# SWITCHING.net
KiCad netlist of a schematic drawn in Altium Designer
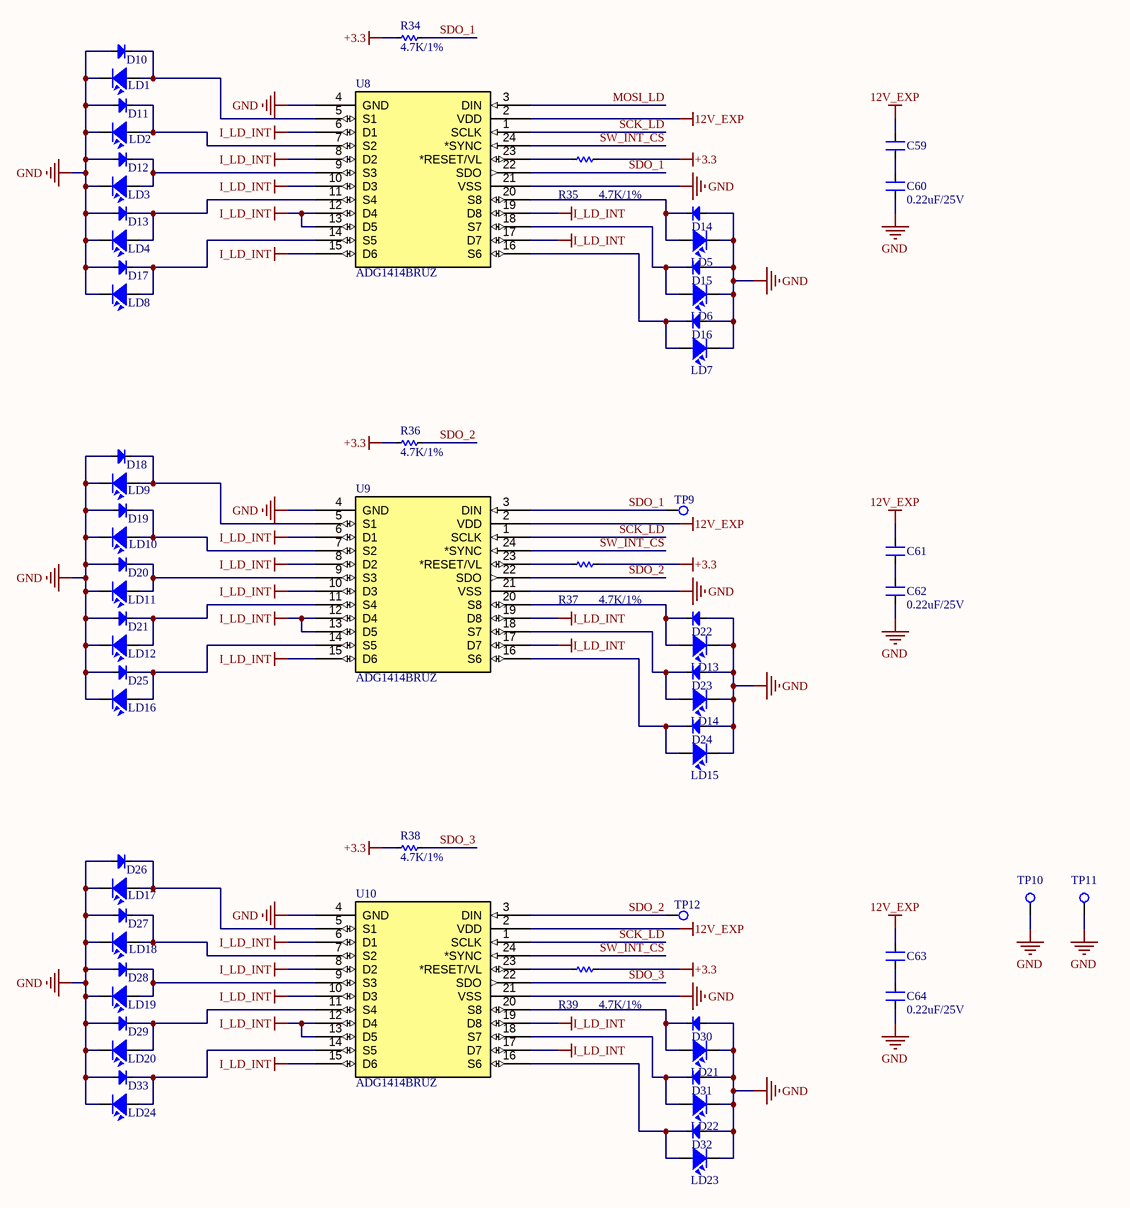
[diagram p0: SWITCHING.SchDoc]

(export (version "E")
  (design (tool "Eeschema 10.0.6"))
  (components
    (comp (ref "C59")
      (value "0.22uF/25V")
      (footprint "SM-0603")
      (description "CL10B224KA8NNNC")
      (libsource (lib "Capacitors") (part "CM"))
    )
    (comp (ref "C60")
      (value "0.22uF/25V")
      (footprint "SM-0603")
      (description "CL10B224KA8NNNC")
      (libsource (lib "Capacitors") (part "CM"))
    )
    (comp (ref "C61")
      (value "0.22uF/25V")
      (footprint "SM-0603")
      (description "CL10B224KA8NNNC")
      (libsource (lib "Capacitors") (part "CM"))
    )
    (comp (ref "C62")
      (value "0.22uF/25V")
      (footprint "SM-0603")
      (description "CL10B224KA8NNNC")
      (libsource (lib "Capacitors") (part "CM"))
    )
    (comp (ref "C63")
      (value "0.22uF/25V")
      (footprint "SM-0603")
      (description "CL10B224KA8NNNC")
      (libsource (lib "Capacitors") (part "CM"))
    )
    (comp (ref "C64")
      (value "0.22uF/25V")
      (footprint "SM-0603")
      (description "CL10B224KA8NNNC")
      (libsource (lib "Capacitors") (part "CM"))
    )
    (comp (ref "D10")
      (value "1N4148W-TP")
      (footprint "SOD23")
      (fields (field (name "PUBLISHER") "Altium Limited"))
      (libsource (lib "Library") (part "Diode SMD"))
    )
    (comp (ref "D11")
      (value "1N4148W-TP")
      (footprint "SOD23")
      (fields (field (name "PUBLISHER") "Altium Limited"))
      (libsource (lib "Library") (part "Diode SMD"))
    )
    (comp (ref "D12")
      (value "1N4148W-TP")
      (footprint "SOD23")
      (fields (field (name "PUBLISHER") "Altium Limited"))
      (libsource (lib "Library") (part "Diode SMD"))
    )
    (comp (ref "D13")
      (value "1N4148W-TP")
      (footprint "SOD23")
      (fields (field (name "PUBLISHER") "Altium Limited"))
      (libsource (lib "Library") (part "Diode SMD"))
    )
    (comp (ref "D14")
      (value "1N4148W-TP")
      (footprint "SOD23")
      (fields (field (name "PUBLISHER") "Altium Limited"))
      (libsource (lib "Library") (part "Diode SMD"))
    )
    (comp (ref "D15")
      (value "1N4148W-TP")
      (footprint "SOD23")
      (fields (field (name "PUBLISHER") "Altium Limited"))
      (libsource (lib "Library") (part "Diode SMD"))
    )
    (comp (ref "D16")
      (value "1N4148W-TP")
      (footprint "SOD23")
      (fields (field (name "PUBLISHER") "Altium Limited"))
      (libsource (lib "Library") (part "Diode SMD"))
    )
    (comp (ref "D17")
      (value "1N4148W-TP")
      (footprint "SOD23")
      (fields (field (name "PUBLISHER") "Altium Limited"))
      (libsource (lib "Library") (part "Diode SMD"))
    )
    (comp (ref "D18")
      (value "1N4148W-TP")
      (footprint "SOD23")
      (fields (field (name "PUBLISHER") "Altium Limited"))
      (libsource (lib "Library") (part "Diode SMD"))
    )
    (comp (ref "D19")
      (value "1N4148W-TP")
      (footprint "SOD23")
      (fields (field (name "PUBLISHER") "Altium Limited"))
      (libsource (lib "Library") (part "Diode SMD"))
    )
    (comp (ref "D20")
      (value "1N4148W-TP")
      (footprint "SOD23")
      (fields (field (name "PUBLISHER") "Altium Limited"))
      (libsource (lib "Library") (part "Diode SMD"))
    )
    (comp (ref "D21")
      (value "1N4148W-TP")
      (footprint "SOD23")
      (fields (field (name "PUBLISHER") "Altium Limited"))
      (libsource (lib "Library") (part "Diode SMD"))
    )
    (comp (ref "D22")
      (value "1N4148W-TP")
      (footprint "SOD23")
      (fields (field (name "PUBLISHER") "Altium Limited"))
      (libsource (lib "Library") (part "Diode SMD"))
    )
    (comp (ref "D23")
      (value "1N4148W-TP")
      (footprint "SOD23")
      (fields (field (name "PUBLISHER") "Altium Limited"))
      (libsource (lib "Library") (part "Diode SMD"))
    )
    (comp (ref "D24")
      (value "1N4148W-TP")
      (footprint "SOD23")
      (fields (field (name "PUBLISHER") "Altium Limited"))
      (libsource (lib "Library") (part "Diode SMD"))
    )
    (comp (ref "D25")
      (value "1N4148W-TP")
      (footprint "SOD23")
      (fields (field (name "PUBLISHER") "Altium Limited"))
      (libsource (lib "Library") (part "Diode SMD"))
    )
    (comp (ref "D26")
      (value "1N4148W-TP")
      (footprint "SOD23")
      (fields (field (name "PUBLISHER") "Altium Limited"))
      (libsource (lib "Library") (part "Diode SMD"))
    )
    (comp (ref "D27")
      (value "1N4148W-TP")
      (footprint "SOD23")
      (fields (field (name "PUBLISHER") "Altium Limited"))
      (libsource (lib "Library") (part "Diode SMD"))
    )
    (comp (ref "D28")
      (value "1N4148W-TP")
      (footprint "SOD23")
      (fields (field (name "PUBLISHER") "Altium Limited"))
      (libsource (lib "Library") (part "Diode SMD"))
    )
    (comp (ref "D29")
      (value "1N4148W-TP")
      (footprint "SOD23")
      (fields (field (name "PUBLISHER") "Altium Limited"))
      (libsource (lib "Library") (part "Diode SMD"))
    )
    (comp (ref "D30")
      (value "1N4148W-TP")
      (footprint "SOD23")
      (fields (field (name "PUBLISHER") "Altium Limited"))
      (libsource (lib "Library") (part "Diode SMD"))
    )
    (comp (ref "D31")
      (value "1N4148W-TP")
      (footprint "SOD23")
      (fields (field (name "PUBLISHER") "Altium Limited"))
      (libsource (lib "Library") (part "Diode SMD"))
    )
    (comp (ref "D32")
      (value "1N4148W-TP")
      (footprint "SOD23")
      (fields (field (name "PUBLISHER") "Altium Limited"))
      (libsource (lib "Library") (part "Diode SMD"))
    )
    (comp (ref "D33")
      (value "1N4148W-TP")
      (footprint "SOD23")
      (fields (field (name "PUBLISHER") "Altium Limited"))
      (libsource (lib "Library") (part "Diode SMD"))
    )
    (comp (ref "LD1")
      (value "LaserDiode")
      (footprint "LASER_SOCKET")
      (description "OPV302")
      (libsource (lib "Library_HUNG") (part "LD"))
    )
    (comp (ref "LD2")
      (value "LaserDiode")
      (footprint "LASER_SOCKET")
      (description "OPV302")
      (libsource (lib "Library_HUNG") (part "LD"))
    )
    (comp (ref "LD3")
      (value "LaserDiode")
      (footprint "LASER_SOCKET")
      (description "OPV302")
      (libsource (lib "Library_HUNG") (part "LD"))
    )
    (comp (ref "LD4")
      (value "LaserDiode")
      (footprint "LASER_SOCKET")
      (description "OPV302")
      (libsource (lib "Library_HUNG") (part "LD"))
    )
    (comp (ref "LD5")
      (value "LaserDiode")
      (footprint "LASER_SOCKET")
      (description "OPV302")
      (libsource (lib "Library_HUNG") (part "LD"))
    )
    (comp (ref "LD6")
      (value "LaserDiode")
      (footprint "LASER_SOCKET")
      (description "OPV302")
      (libsource (lib "Library_HUNG") (part "LD"))
    )
    (comp (ref "LD7")
      (value "LaserDiode")
      (footprint "LASER_SOCKET")
      (description "OPV302")
      (libsource (lib "Library_HUNG") (part "LD"))
    )
    (comp (ref "LD8")
      (value "LaserDiode")
      (footprint "LASER_SOCKET")
      (description "OPV302")
      (libsource (lib "Library_HUNG") (part "LD"))
    )
    (comp (ref "LD9")
      (value "LaserDiode")
      (footprint "LASER_SOCKET")
      (description "OPV302")
      (libsource (lib "Library_HUNG") (part "LD"))
    )
    (comp (ref "LD10")
      (value "LaserDiode")
      (footprint "LASER_SOCKET")
      (description "OPV302")
      (libsource (lib "Library_HUNG") (part "LD"))
    )
    (comp (ref "LD11")
      (value "LaserDiode")
      (footprint "LASER_SOCKET")
      (description "OPV302")
      (libsource (lib "Library_HUNG") (part "LD"))
    )
    (comp (ref "LD12")
      (value "LaserDiode")
      (footprint "LASER_SOCKET")
      (description "OPV302")
      (libsource (lib "Library_HUNG") (part "LD"))
    )
    (comp (ref "LD13")
      (value "LaserDiode")
      (footprint "LASER_SOCKET")
      (description "OPV302")
      (libsource (lib "Library_HUNG") (part "LD"))
    )
    (comp (ref "LD14")
      (value "LaserDiode")
      (footprint "LASER_SOCKET")
      (description "OPV302")
      (libsource (lib "Library_HUNG") (part "LD"))
    )
    (comp (ref "LD15")
      (value "LaserDiode")
      (footprint "LASER_SOCKET")
      (description "OPV302")
      (libsource (lib "Library_HUNG") (part "LD"))
    )
    (comp (ref "LD16")
      (value "LaserDiode")
      (footprint "LASER_SOCKET")
      (description "OPV302")
      (libsource (lib "Library_HUNG") (part "LD"))
    )
    (comp (ref "LD17")
      (value "LaserDiode")
      (footprint "LASER_SOCKET")
      (description "OPV302")
      (libsource (lib "Library_HUNG") (part "LD"))
    )
    (comp (ref "LD18")
      (value "LaserDiode")
      (footprint "LASER_SOCKET")
      (description "OPV302")
      (libsource (lib "Library_HUNG") (part "LD"))
    )
    (comp (ref "LD19")
      (value "LaserDiode")
      (footprint "LASER_SOCKET")
      (description "OPV302")
      (libsource (lib "Library_HUNG") (part "LD"))
    )
    (comp (ref "LD20")
      (value "LaserDiode")
      (footprint "LASER_SOCKET")
      (description "OPV302")
      (libsource (lib "Library_HUNG") (part "LD"))
    )
    (comp (ref "LD21")
      (value "LaserDiode")
      (footprint "LASER_SOCKET")
      (description "OPV302")
      (libsource (lib "Library_HUNG") (part "LD"))
    )
    (comp (ref "LD22")
      (value "LaserDiode")
      (footprint "LASER_SOCKET")
      (description "OPV302")
      (libsource (lib "Library_HUNG") (part "LD"))
    )
    (comp (ref "LD23")
      (value "LaserDiode")
      (footprint "LASER_SOCKET")
      (description "OPV302")
      (libsource (lib "Library_HUNG") (part "LD"))
    )
    (comp (ref "LD24")
      (value "LaserDiode")
      (footprint "LASER_SOCKET")
      (description "OPV302")
      (libsource (lib "Library_HUNG") (part "LD"))
    )
    (comp (ref "R34")
      (value "4.7K/1%")
      (footprint "RES-SMD-0603")
      (description "ERJ-3EKF4701V")
      (fields
        (field (name "MANUFACTURER") "Generic Components")
        (field (name "PUBLISHER") "Altium Hobart Technology Centre")
      )
      (libsource (lib "Library") (part "Res-SMD"))
    )
    (comp (ref "R35")
      (value "4.7K/1%")
      (footprint "RES-SMD-0603")
      (description "ERJ-3EKF4701V")
      (fields
        (field (name "MANUFACTURER") "Generic Components")
        (field (name "PUBLISHER") "Altium Hobart Technology Centre")
      )
      (libsource (lib "Library") (part "Res-SMD"))
    )
    (comp (ref "R36")
      (value "4.7K/1%")
      (footprint "RES-SMD-0603")
      (description "ERJ-3EKF4701V")
      (fields
        (field (name "MANUFACTURER") "Generic Components")
        (field (name "PUBLISHER") "Altium Hobart Technology Centre")
      )
      (libsource (lib "Library") (part "Res-SMD"))
    )
    (comp (ref "R37")
      (value "4.7K/1%")
      (footprint "RES-SMD-0603")
      (description "ERJ-3EKF4701V")
      (fields
        (field (name "MANUFACTURER") "Generic Components")
        (field (name "PUBLISHER") "Altium Hobart Technology Centre")
      )
      (libsource (lib "Library") (part "Res-SMD"))
    )
    (comp (ref "R38")
      (value "4.7K/1%")
      (footprint "RES-SMD-0603")
      (description "ERJ-3EKF4701V")
      (fields
        (field (name "MANUFACTURER") "Generic Components")
        (field (name "PUBLISHER") "Altium Hobart Technology Centre")
      )
      (libsource (lib "Library") (part "Res-SMD"))
    )
    (comp (ref "R39")
      (value "4.7K/1%")
      (footprint "RES-SMD-0603")
      (description "ERJ-3EKF4701V")
      (fields
        (field (name "MANUFACTURER") "Generic Components")
        (field (name "PUBLISHER") "Altium Hobart Technology Centre")
      )
      (libsource (lib "Library") (part "Res-SMD"))
    )
    (comp (ref "TP9")
      (value "Test_Point")
      (footprint "TESTPOINT")
      (libsource (lib "Library_HUNG") (part "Test_Point"))
    )
    (comp (ref "TP10")
      (value "Test_Point")
      (footprint "TESTPOINT")
      (libsource (lib "Library_HUNG") (part "Test_Point"))
    )
    (comp (ref "TP11")
      (value "Test_Point")
      (footprint "TESTPOINT")
      (libsource (lib "Library_HUNG") (part "Test_Point"))
    )
    (comp (ref "TP12")
      (value "Test_Point")
      (footprint "TESTPOINT")
      (libsource (lib "Library_HUNG") (part "Test_Point"))
    )
    (comp (ref "U8")
      (value "ADG1414BRUZ")
      (footprint "TSSOP24")
      (libsource (lib "Library_HUNG") (part "ADG1414BRUZ"))
    )
    (comp (ref "U9")
      (value "ADG1414BRUZ")
      (footprint "TSSOP24")
      (libsource (lib "Library_HUNG") (part "ADG1414BRUZ"))
    )
    (comp (ref "U10")
      (value "ADG1414BRUZ")
      (footprint "TSSOP24")
      (libsource (lib "Library_HUNG") (part "ADG1414BRUZ"))
    )
  )
  (nets
    (net (code "1") (name "+3.3") (class "Default")
      (node (ref "R34") (pin "2") (pinfunction "2_2") (pintype "passive"))
      (node (ref "R35") (pin "2") (pinfunction "2_2") (pintype "passive"))
      (node (ref "R36") (pin "2") (pinfunction "2_2") (pintype "passive"))
      (node (ref "R37") (pin "2") (pinfunction "2_2") (pintype "passive"))
      (node (ref "R38") (pin "2") (pinfunction "2_2") (pintype "passive"))
      (node (ref "R39") (pin "2") (pinfunction "2_2") (pintype "passive"))
    )
    (net (code "2") (name "/MOSI_LD") (class "Default")
      (node (ref "U8") (pin "3") (pinfunction "DIN_3") (pintype "input"))
    )
    (net (code "3") (name "/SCK_LD") (class "Default")
      (node (ref "U10") (pin "1") (pinfunction "SCLK_1") (pintype "input"))
      (node (ref "U8") (pin "1") (pinfunction "SCLK_1") (pintype "input"))
      (node (ref "U9") (pin "1") (pinfunction "SCLK_1") (pintype "input"))
    )
    (net (code "4") (name "/SDO_1") (class "Default")
      (node (ref "R34") (pin "1") (pinfunction "1_1") (pintype "passive"))
      (node (ref "TP9") (pin "1") (pintype "power_in"))
      (node (ref "U8") (pin "22") (pinfunction "SDO_22") (pintype "output"))
      (node (ref "U9") (pin "3") (pinfunction "DIN_3") (pintype "input"))
    )
    (net (code "5") (name "/SDO_2") (class "Default")
      (node (ref "R36") (pin "1") (pinfunction "1_1") (pintype "passive"))
      (node (ref "TP12") (pin "1") (pintype "power_in"))
      (node (ref "U10") (pin "3") (pinfunction "DIN_3") (pintype "input"))
      (node (ref "U9") (pin "22") (pinfunction "SDO_22") (pintype "output"))
    )
    (net (code "6") (name "/SDO_3") (class "Default")
      (node (ref "R38") (pin "1") (pinfunction "1_1") (pintype "passive"))
      (node (ref "U10") (pin "22") (pinfunction "SDO_22") (pintype "output"))
    )
    (net (code "7") (name "/SW_INT_CS") (class "Default")
      (node (ref "U10") (pin "24") (pinfunction "*SYNC_24") (pintype "input"))
      (node (ref "U8") (pin "24") (pinfunction "*SYNC_24") (pintype "input"))
      (node (ref "U9") (pin "24") (pinfunction "*SYNC_24") (pintype "input"))
    )
    (net (code "8") (name "12V_EXP") (class "Default")
      (node (ref "C59") (pin "2") (pinfunction "2_2") (pintype "passive"))
      (node (ref "C61") (pin "2") (pinfunction "2_2") (pintype "passive"))
      (node (ref "C63") (pin "2") (pinfunction "2_2") (pintype "passive"))
      (node (ref "U10") (pin "2") (pinfunction "VDD_2") (pintype "power_in"))
      (node (ref "U8") (pin "2") (pinfunction "VDD_2") (pintype "power_in"))
      (node (ref "U9") (pin "2") (pinfunction "VDD_2") (pintype "power_in"))
    )
    (net (code "9") (name "GND") (class "Default")
      (node (ref "C60") (pin "1") (pinfunction "1_1") (pintype "passive"))
      (node (ref "C62") (pin "1") (pinfunction "1_1") (pintype "passive"))
      (node (ref "C64") (pin "1") (pinfunction "1_1") (pintype "passive"))
      (node (ref "D10") (pin "1") (pinfunction "A_1") (pintype "passive"))
      (node (ref "D11") (pin "1") (pinfunction "A_1") (pintype "passive"))
      (node (ref "D12") (pin "1") (pinfunction "A_1") (pintype "passive"))
      (node (ref "D13") (pin "1") (pinfunction "A_1") (pintype "passive"))
      (node (ref "D14") (pin "1") (pinfunction "A_1") (pintype "passive"))
      (node (ref "D15") (pin "1") (pinfunction "A_1") (pintype "passive"))
      (node (ref "D16") (pin "1") (pinfunction "A_1") (pintype "passive"))
      (node (ref "D17") (pin "1") (pinfunction "A_1") (pintype "passive"))
      (node (ref "D18") (pin "1") (pinfunction "A_1") (pintype "passive"))
      (node (ref "D19") (pin "1") (pinfunction "A_1") (pintype "passive"))
      (node (ref "D20") (pin "1") (pinfunction "A_1") (pintype "passive"))
      (node (ref "D21") (pin "1") (pinfunction "A_1") (pintype "passive"))
      (node (ref "D22") (pin "1") (pinfunction "A_1") (pintype "passive"))
      (node (ref "D23") (pin "1") (pinfunction "A_1") (pintype "passive"))
      (node (ref "D24") (pin "1") (pinfunction "A_1") (pintype "passive"))
      (node (ref "D25") (pin "1") (pinfunction "A_1") (pintype "passive"))
      (node (ref "D26") (pin "1") (pinfunction "A_1") (pintype "passive"))
      (node (ref "D27") (pin "1") (pinfunction "A_1") (pintype "passive"))
      (node (ref "D28") (pin "1") (pinfunction "A_1") (pintype "passive"))
      (node (ref "D29") (pin "1") (pinfunction "A_1") (pintype "passive"))
      (node (ref "D30") (pin "1") (pinfunction "A_1") (pintype "passive"))
      (node (ref "D31") (pin "1") (pinfunction "A_1") (pintype "passive"))
      (node (ref "D32") (pin "1") (pinfunction "A_1") (pintype "passive"))
      (node (ref "D33") (pin "1") (pinfunction "A_1") (pintype "passive"))
      (node (ref "LD1") (pin "3") (pinfunction "3_3") (pintype "passive"))
      (node (ref "LD10") (pin "3") (pinfunction "3_3") (pintype "passive"))
      (node (ref "LD11") (pin "3") (pinfunction "3_3") (pintype "passive"))
      (node (ref "LD12") (pin "3") (pinfunction "3_3") (pintype "passive"))
      (node (ref "LD13") (pin "3") (pinfunction "3_3") (pintype "passive"))
      (node (ref "LD14") (pin "3") (pinfunction "3_3") (pintype "passive"))
      (node (ref "LD15") (pin "3") (pinfunction "3_3") (pintype "passive"))
      (node (ref "LD16") (pin "3") (pinfunction "3_3") (pintype "passive"))
      (node (ref "LD17") (pin "3") (pinfunction "3_3") (pintype "passive"))
      (node (ref "LD18") (pin "3") (pinfunction "3_3") (pintype "passive"))
      (node (ref "LD19") (pin "3") (pinfunction "3_3") (pintype "passive"))
      (node (ref "LD2") (pin "3") (pinfunction "3_3") (pintype "passive"))
      (node (ref "LD20") (pin "3") (pinfunction "3_3") (pintype "passive"))
      (node (ref "LD21") (pin "3") (pinfunction "3_3") (pintype "passive"))
      (node (ref "LD22") (pin "3") (pinfunction "3_3") (pintype "passive"))
      (node (ref "LD23") (pin "3") (pinfunction "3_3") (pintype "passive"))
      (node (ref "LD24") (pin "3") (pinfunction "3_3") (pintype "passive"))
      (node (ref "LD3") (pin "3") (pinfunction "3_3") (pintype "passive"))
      (node (ref "LD4") (pin "3") (pinfunction "3_3") (pintype "passive"))
      (node (ref "LD5") (pin "3") (pinfunction "3_3") (pintype "passive"))
      (node (ref "LD6") (pin "3") (pinfunction "3_3") (pintype "passive"))
      (node (ref "LD7") (pin "3") (pinfunction "3_3") (pintype "passive"))
      (node (ref "LD8") (pin "3") (pinfunction "3_3") (pintype "passive"))
      (node (ref "LD9") (pin "3") (pinfunction "3_3") (pintype "passive"))
      (node (ref "TP10") (pin "1") (pintype "power_in"))
      (node (ref "TP11") (pin "1") (pintype "power_in"))
      (node (ref "U10") (pin "21") (pinfunction "VSS_21") (pintype "power_in"))
      (node (ref "U10") (pin "4") (pinfunction "GND_4") (pintype "power_in"))
      (node (ref "U8") (pin "21") (pinfunction "VSS_21") (pintype "power_in"))
      (node (ref "U8") (pin "4") (pinfunction "GND_4") (pintype "power_in"))
      (node (ref "U9") (pin "21") (pinfunction "VSS_21") (pintype "power_in"))
      (node (ref "U9") (pin "4") (pinfunction "GND_4") (pintype "power_in"))
    )
    (net (code "10") (name "I_LD_INT") (class "Default")
      (node (ref "U10") (pin "10") (pinfunction "D3_10") (pintype "bidirectional"))
      (node (ref "U10") (pin "12") (pinfunction "D4_12") (pintype "bidirectional"))
      (node (ref "U10") (pin "13") (pinfunction "D5_13") (pintype "bidirectional"))
      (node (ref "U10") (pin "15") (pinfunction "D6_15") (pintype "bidirectional"))
      (node (ref "U10") (pin "17") (pinfunction "D7_17") (pintype "bidirectional"))
      (node (ref "U10") (pin "19") (pinfunction "D8_19") (pintype "bidirectional"))
      (node (ref "U10") (pin "6") (pinfunction "D1_6") (pintype "bidirectional"))
      (node (ref "U10") (pin "8") (pinfunction "D2_8") (pintype "bidirectional"))
      (node (ref "U8") (pin "10") (pinfunction "D3_10") (pintype "bidirectional"))
      (node (ref "U8") (pin "12") (pinfunction "D4_12") (pintype "bidirectional"))
      (node (ref "U8") (pin "13") (pinfunction "D5_13") (pintype "bidirectional"))
      (node (ref "U8") (pin "15") (pinfunction "D6_15") (pintype "bidirectional"))
      (node (ref "U8") (pin "17") (pinfunction "D7_17") (pintype "bidirectional"))
      (node (ref "U8") (pin "19") (pinfunction "D8_19") (pintype "bidirectional"))
      (node (ref "U8") (pin "6") (pinfunction "D1_6") (pintype "bidirectional"))
      (node (ref "U8") (pin "8") (pinfunction "D2_8") (pintype "bidirectional"))
      (node (ref "U9") (pin "10") (pinfunction "D3_10") (pintype "bidirectional"))
      (node (ref "U9") (pin "12") (pinfunction "D4_12") (pintype "bidirectional"))
      (node (ref "U9") (pin "13") (pinfunction "D5_13") (pintype "bidirectional"))
      (node (ref "U9") (pin "15") (pinfunction "D6_15") (pintype "bidirectional"))
      (node (ref "U9") (pin "17") (pinfunction "D7_17") (pintype "bidirectional"))
      (node (ref "U9") (pin "19") (pinfunction "D8_19") (pintype "bidirectional"))
      (node (ref "U9") (pin "6") (pinfunction "D1_6") (pintype "bidirectional"))
      (node (ref "U9") (pin "8") (pinfunction "D2_8") (pintype "bidirectional"))
    )
    (net (code "11") (name "Net-(C59-Pad1)") (class "Default")
      (node (ref "C59") (pin "1") (pinfunction "1_1") (pintype "passive"))
      (node (ref "C60") (pin "2") (pinfunction "2_2") (pintype "passive"))
    )
    (net (code "12") (name "Net-(C61-Pad1)") (class "Default")
      (node (ref "C61") (pin "1") (pinfunction "1_1") (pintype "passive"))
      (node (ref "C62") (pin "2") (pinfunction "2_2") (pintype "passive"))
    )
    (net (code "13") (name "Net-(C63-Pad1)") (class "Default")
      (node (ref "C63") (pin "1") (pinfunction "1_1") (pintype "passive"))
      (node (ref "C64") (pin "2") (pinfunction "2_2") (pintype "passive"))
    )
    (net (code "14") (name "Net-(D10-K)") (class "Default")
      (node (ref "D10") (pin "2") (pinfunction "K_2") (pintype "passive"))
      (node (ref "LD1") (pin "1") (pinfunction "1_1") (pintype "passive"))
      (node (ref "U8") (pin "5") (pinfunction "S1_5") (pintype "bidirectional"))
    )
    (net (code "15") (name "Net-(D11-K)") (class "Default")
      (node (ref "D11") (pin "2") (pinfunction "K_2") (pintype "passive"))
      (node (ref "LD2") (pin "1") (pinfunction "1_1") (pintype "passive"))
      (node (ref "U8") (pin "7") (pinfunction "S2_7") (pintype "bidirectional"))
    )
    (net (code "16") (name "Net-(D12-K)") (class "Default")
      (node (ref "D12") (pin "2") (pinfunction "K_2") (pintype "passive"))
      (node (ref "LD3") (pin "1") (pinfunction "1_1") (pintype "passive"))
      (node (ref "U8") (pin "9") (pinfunction "S3_9") (pintype "bidirectional"))
    )
    (net (code "17") (name "Net-(D13-K)") (class "Default")
      (node (ref "D13") (pin "2") (pinfunction "K_2") (pintype "passive"))
      (node (ref "LD4") (pin "1") (pinfunction "1_1") (pintype "passive"))
      (node (ref "U8") (pin "11") (pinfunction "S4_11") (pintype "bidirectional"))
    )
    (net (code "18") (name "Net-(D14-K)") (class "Default")
      (node (ref "D14") (pin "2") (pinfunction "K_2") (pintype "passive"))
      (node (ref "LD5") (pin "1") (pinfunction "1_1") (pintype "passive"))
      (node (ref "U8") (pin "20") (pinfunction "S8_20") (pintype "bidirectional"))
    )
    (net (code "19") (name "Net-(D15-K)") (class "Default")
      (node (ref "D15") (pin "2") (pinfunction "K_2") (pintype "passive"))
      (node (ref "LD6") (pin "1") (pinfunction "1_1") (pintype "passive"))
      (node (ref "U8") (pin "18") (pinfunction "S7_18") (pintype "bidirectional"))
    )
    (net (code "20") (name "Net-(D16-K)") (class "Default")
      (node (ref "D16") (pin "2") (pinfunction "K_2") (pintype "passive"))
      (node (ref "LD7") (pin "1") (pinfunction "1_1") (pintype "passive"))
      (node (ref "U8") (pin "16") (pinfunction "S6_16") (pintype "bidirectional"))
    )
    (net (code "21") (name "Net-(D17-K)") (class "Default")
      (node (ref "D17") (pin "2") (pinfunction "K_2") (pintype "passive"))
      (node (ref "LD8") (pin "1") (pinfunction "1_1") (pintype "passive"))
      (node (ref "U8") (pin "14") (pinfunction "S5_14") (pintype "bidirectional"))
    )
    (net (code "22") (name "Net-(D18-K)") (class "Default")
      (node (ref "D18") (pin "2") (pinfunction "K_2") (pintype "passive"))
      (node (ref "LD9") (pin "1") (pinfunction "1_1") (pintype "passive"))
      (node (ref "U9") (pin "5") (pinfunction "S1_5") (pintype "bidirectional"))
    )
    (net (code "23") (name "Net-(D19-K)") (class "Default")
      (node (ref "D19") (pin "2") (pinfunction "K_2") (pintype "passive"))
      (node (ref "LD10") (pin "1") (pinfunction "1_1") (pintype "passive"))
      (node (ref "U9") (pin "7") (pinfunction "S2_7") (pintype "bidirectional"))
    )
    (net (code "24") (name "Net-(D20-K)") (class "Default")
      (node (ref "D20") (pin "2") (pinfunction "K_2") (pintype "passive"))
      (node (ref "LD11") (pin "1") (pinfunction "1_1") (pintype "passive"))
      (node (ref "U9") (pin "9") (pinfunction "S3_9") (pintype "bidirectional"))
    )
    (net (code "25") (name "Net-(D21-K)") (class "Default")
      (node (ref "D21") (pin "2") (pinfunction "K_2") (pintype "passive"))
      (node (ref "LD12") (pin "1") (pinfunction "1_1") (pintype "passive"))
      (node (ref "U9") (pin "11") (pinfunction "S4_11") (pintype "bidirectional"))
    )
    (net (code "26") (name "Net-(D22-K)") (class "Default")
      (node (ref "D22") (pin "2") (pinfunction "K_2") (pintype "passive"))
      (node (ref "LD13") (pin "1") (pinfunction "1_1") (pintype "passive"))
      (node (ref "U9") (pin "20") (pinfunction "S8_20") (pintype "bidirectional"))
    )
    (net (code "27") (name "Net-(D23-K)") (class "Default")
      (node (ref "D23") (pin "2") (pinfunction "K_2") (pintype "passive"))
      (node (ref "LD14") (pin "1") (pinfunction "1_1") (pintype "passive"))
      (node (ref "U9") (pin "18") (pinfunction "S7_18") (pintype "bidirectional"))
    )
    (net (code "28") (name "Net-(D24-K)") (class "Default")
      (node (ref "D24") (pin "2") (pinfunction "K_2") (pintype "passive"))
      (node (ref "LD15") (pin "1") (pinfunction "1_1") (pintype "passive"))
      (node (ref "U9") (pin "16") (pinfunction "S6_16") (pintype "bidirectional"))
    )
    (net (code "29") (name "Net-(D25-K)") (class "Default")
      (node (ref "D25") (pin "2") (pinfunction "K_2") (pintype "passive"))
      (node (ref "LD16") (pin "1") (pinfunction "1_1") (pintype "passive"))
      (node (ref "U9") (pin "14") (pinfunction "S5_14") (pintype "bidirectional"))
    )
    (net (code "30") (name "Net-(D26-K)") (class "Default")
      (node (ref "D26") (pin "2") (pinfunction "K_2") (pintype "passive"))
      (node (ref "LD17") (pin "1") (pinfunction "1_1") (pintype "passive"))
      (node (ref "U10") (pin "5") (pinfunction "S1_5") (pintype "bidirectional"))
    )
    (net (code "31") (name "Net-(D27-K)") (class "Default")
      (node (ref "D27") (pin "2") (pinfunction "K_2") (pintype "passive"))
      (node (ref "LD18") (pin "1") (pinfunction "1_1") (pintype "passive"))
      (node (ref "U10") (pin "7") (pinfunction "S2_7") (pintype "bidirectional"))
    )
    (net (code "32") (name "Net-(D28-K)") (class "Default")
      (node (ref "D28") (pin "2") (pinfunction "K_2") (pintype "passive"))
      (node (ref "LD19") (pin "1") (pinfunction "1_1") (pintype "passive"))
      (node (ref "U10") (pin "9") (pinfunction "S3_9") (pintype "bidirectional"))
    )
    (net (code "33") (name "Net-(D29-K)") (class "Default")
      (node (ref "D29") (pin "2") (pinfunction "K_2") (pintype "passive"))
      (node (ref "LD20") (pin "1") (pinfunction "1_1") (pintype "passive"))
      (node (ref "U10") (pin "11") (pinfunction "S4_11") (pintype "bidirectional"))
    )
    (net (code "34") (name "Net-(D30-K)") (class "Default")
      (node (ref "D30") (pin "2") (pinfunction "K_2") (pintype "passive"))
      (node (ref "LD21") (pin "1") (pinfunction "1_1") (pintype "passive"))
      (node (ref "U10") (pin "20") (pinfunction "S8_20") (pintype "bidirectional"))
    )
    (net (code "35") (name "Net-(D31-K)") (class "Default")
      (node (ref "D31") (pin "2") (pinfunction "K_2") (pintype "passive"))
      (node (ref "LD22") (pin "1") (pinfunction "1_1") (pintype "passive"))
      (node (ref "U10") (pin "18") (pinfunction "S7_18") (pintype "bidirectional"))
    )
    (net (code "36") (name "Net-(D32-K)") (class "Default")
      (node (ref "D32") (pin "2") (pinfunction "K_2") (pintype "passive"))
      (node (ref "LD23") (pin "1") (pinfunction "1_1") (pintype "passive"))
      (node (ref "U10") (pin "16") (pinfunction "S6_16") (pintype "bidirectional"))
    )
    (net (code "37") (name "Net-(D33-K)") (class "Default")
      (node (ref "D33") (pin "2") (pinfunction "K_2") (pintype "passive"))
      (node (ref "LD24") (pin "1") (pinfunction "1_1") (pintype "passive"))
      (node (ref "U10") (pin "14") (pinfunction "S5_14") (pintype "bidirectional"))
    )
    (net (code "38") (name "Net-(U8-*RESET{slash}VL)") (class "Default")
      (node (ref "R35") (pin "1") (pinfunction "1_1") (pintype "passive"))
      (node (ref "U8") (pin "23") (pinfunction "*RESET/VL_23") (pintype "bidirectional"))
    )
    (net (code "39") (name "Net-(U9-*RESET{slash}VL)") (class "Default")
      (node (ref "R37") (pin "1") (pinfunction "1_1") (pintype "passive"))
      (node (ref "U9") (pin "23") (pinfunction "*RESET/VL_23") (pintype "bidirectional"))
    )
    (net (code "40") (name "Net-(U10-*RESET{slash}VL)") (class "Default")
      (node (ref "R39") (pin "1") (pinfunction "1_1") (pintype "passive"))
      (node (ref "U10") (pin "23") (pinfunction "*RESET/VL_23") (pintype "bidirectional"))
    )
  )
)
